# Power.net
KiCad netlist of a schematic drawn in Altium Designer
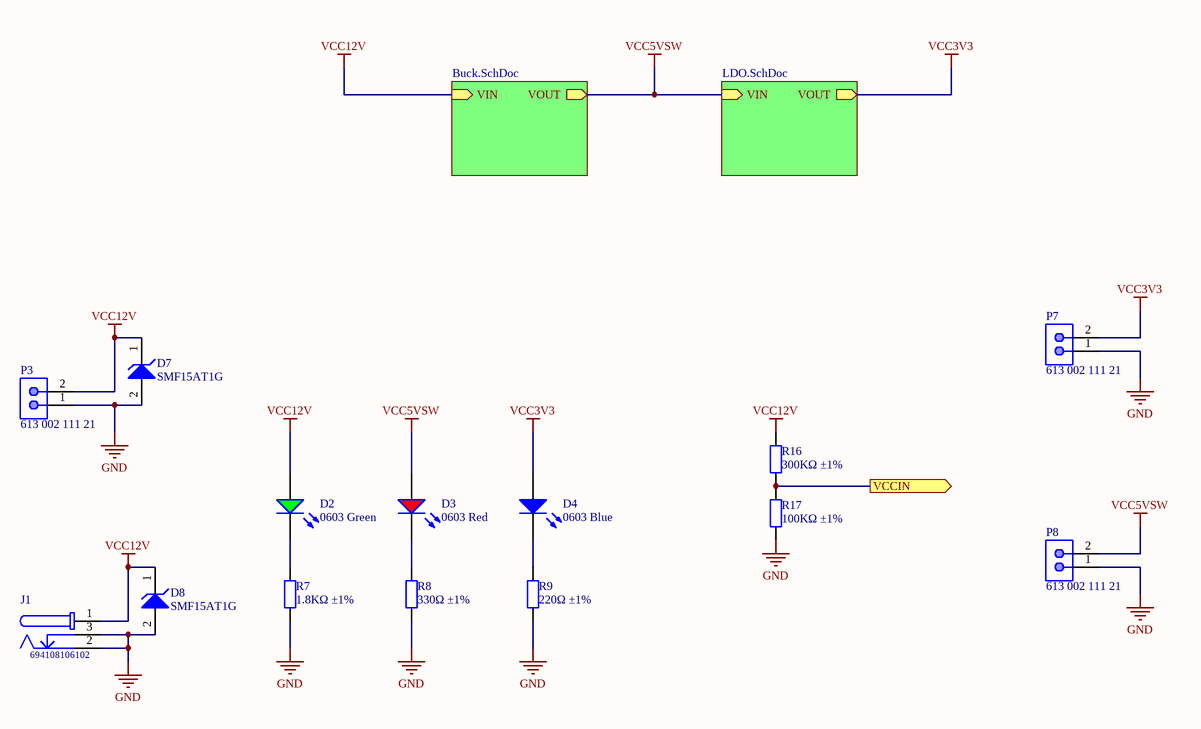
[diagram p0: Power.SchDoc]

(export (version "E")
  (design (tool "Eeschema 10.0.6"))
  (components
    (comp (ref "D2")
      (value "0603 Green")
      (footprint "0603_LED_S1")
      (description "LED")
      (libsource (lib "Miscellaneous Devices LC") (part "0603 LED Green"))
    )
    (comp (ref "D3")
      (value "0603 Red")
      (footprint "0603_LED_S1")
      (description "LED")
      (libsource (lib "Miscellaneous Devices LC") (part "0603 LED Red"))
    )
    (comp (ref "D4")
      (value "0603 Blue")
      (footprint "0603_LED_S1")
      (description "LED")
      (libsource (lib "Miscellaneous Devices LC") (part "0603 LED Blue"))
    )
    (comp (ref "D7")
      (value "SMF15AT1G")
      (footprint "ONSC-SOD-123FL-2-498_V")
      (description "200 W Transient Voltage Suppressor, 2-Pin SOD-123FL, Pb-Free, Tape and Reel")
      (fields (field (name "MANUFACTURER") "On Semiconductor"))
      (libsource (lib "Altium Content Vault") (part "ONSC-K1A2-2"))
    )
    (comp (ref "D8")
      (value "SMF15AT1G")
      (footprint "ONSC-SOD-123FL-2-498_V")
      (description "200 W Transient Voltage Suppressor, 2-Pin SOD-123FL, Pb-Free, Tape and Reel")
      (fields (field (name "MANUFACTURER") "On Semiconductor"))
      (libsource (lib "Altium Content Vault") (part "ONSC-K1A2-2"))
    )
    (comp (ref "J1")
      (value "694108106102")
      (footprint "694108106102")
      (description "DC Power Jack Connector with 4 soldering pads & Pegs WR-DC, Male, Right Angled, SMT, 5 A, 24 V")
      (fields (field (name "MANUFACTURER") "Wurth Elektronik") (field (name "PUBLISHER") "WurthElektronik"))
      (libsource (lib "Altium Content Vault") (part "WE-JACK-2CD3-RN"))
    )
    (comp (ref "P3")
      (value "613 002 111 21")
      (footprint "WE-61300211121_V")
      (libsource (lib "Altium Content Vault") (part "CN-1P-M-R2"))
    )
    (comp (ref "P7")
      (value "613 002 111 21")
      (footprint "WE-61300211121_V")
      (libsource (lib "Altium Content Vault") (part "CN-1P-M-R2"))
    )
    (comp (ref "P8")
      (value "613 002 111 21")
      (footprint "WE-61300211121_V")
      (libsource (lib "Altium Content Vault") (part "CN-1P-M-R2"))
    )
    (comp (ref "R7")
      (value "1.8KΩ ±1%")
      (footprint "0603_R")
      (description "Chip resistor")
      (fields (field (name "MANUFACTURER") "Uniroyal Elec") (field (name "PARTNUMBER") "0603WAF1801T5E"))
      (libsource (lib "Miscellaneous Devices LC") (part "0603 1.8K (1801) 1%"))
    )
    (comp (ref "R8")
      (value "330Ω ±1%")
      (footprint "0603_R")
      (description "Chip resistor")
      (fields (field (name "MANUFACTURER") "Uniroyal Elec") (field (name "PARTNUMBER") "0603WAF3300T5E"))
      (libsource (lib "Miscellaneous Devices LC") (part "0603 330R (3300) 1%"))
    )
    (comp (ref "R9")
      (value "220Ω ±1%")
      (footprint "0603_R")
      (description "Chip resistor")
      (fields (field (name "MANUFACTURER") "Uniroyal Elec") (field (name "PARTNUMBER") "0603WAF2200T5E"))
      (libsource (lib "Miscellaneous Devices LC") (part "0603 220R (2200) 1%"))
    )
    (comp (ref "R16")
      (value "300KΩ ±1%")
      (footprint "0402_R")
      (description "Chip resistor")
      (fields (field (name "MANUFACTURER") "Uniroyal Elec") (field (name "PARTNUMBER") "0402WGF3003TCE"))
      (libsource (lib "Miscellaneous Devices LC") (part "0402 300K (3003) 1%"))
    )
    (comp (ref "R17")
      (value "100KΩ ±1%")
      (footprint "0402_R")
      (description "Chip resistor")
      (fields (field (name "MANUFACTURER") "Uniroyal Elec") (field (name "PARTNUMBER") "0402WGF1003TCE"))
      (libsource (lib "Miscellaneous Devices LC") (part "0402 100K (1003) 1%"))
    )
  )
  (nets
    (net (code "1") (name "/VCCIN") (class "Default")
      (node (ref "R16") (pin "1") (pinfunction "1_1") (pintype "passive"))
      (node (ref "R17") (pin "2") (pinfunction "2_2") (pintype "passive"))
    )
    (net (code "2") (name "GND") (class "Default")
      (node (ref "D7") (pin "2") (pinfunction "A_2") (pintype "passive"))
      (node (ref "D8") (pin "2") (pinfunction "A_2") (pintype "passive"))
      (node (ref "J1") (pin "2") (pinfunction "2_2") (pintype "passive"))
      (node (ref "J1") (pin "3") (pinfunction "3_3") (pintype "passive"))
      (node (ref "P3") (pin "1") (pinfunction "1_1") (pintype "passive"))
      (node (ref "P7") (pin "1") (pinfunction "1_1") (pintype "passive"))
      (node (ref "P8") (pin "1") (pinfunction "1_1") (pintype "passive"))
      (node (ref "R17") (pin "1") (pinfunction "1_1") (pintype "passive"))
      (node (ref "R7") (pin "1") (pinfunction "1_1") (pintype "passive"))
      (node (ref "R8") (pin "1") (pinfunction "1_1") (pintype "passive"))
      (node (ref "R9") (pin "1") (pinfunction "1_1") (pintype "passive"))
    )
    (net (code "3") (name "Net-(D2-PadK)") (class "Default")
      (node (ref "D2") (pin "K") (pinfunction "K_K") (pintype "passive"))
      (node (ref "R7") (pin "2") (pinfunction "2_2") (pintype "passive"))
    )
    (net (code "4") (name "Net-(D3-PadK)") (class "Default")
      (node (ref "D3") (pin "K") (pinfunction "K_K") (pintype "passive"))
      (node (ref "R8") (pin "2") (pinfunction "2_2") (pintype "passive"))
    )
    (net (code "5") (name "Net-(D4-PadK)") (class "Default")
      (node (ref "D4") (pin "K") (pinfunction "K_K") (pintype "passive"))
      (node (ref "R9") (pin "2") (pinfunction "2_2") (pintype "passive"))
    )
    (net (code "6") (name "VCC3V3") (class "Default")
      (node (ref "D4") (pin "A") (pinfunction "A_A") (pintype "passive"))
      (node (ref "P7") (pin "2") (pinfunction "2_2") (pintype "passive"))
    )
    (net (code "7") (name "VCC5VSW") (class "Default")
      (node (ref "D3") (pin "A") (pinfunction "A_A") (pintype "passive"))
      (node (ref "P8") (pin "2") (pinfunction "2_2") (pintype "passive"))
    )
    (net (code "8") (name "VCC12V") (class "Default")
      (node (ref "D2") (pin "A") (pinfunction "A_A") (pintype "passive"))
      (node (ref "D7") (pin "1") (pinfunction "K_1") (pintype "passive"))
      (node (ref "D8") (pin "1") (pinfunction "K_1") (pintype "passive"))
      (node (ref "J1") (pin "1") (pinfunction "1_1") (pintype "passive"))
      (node (ref "P3") (pin "2") (pinfunction "2_2") (pintype "passive"))
      (node (ref "R16") (pin "2") (pinfunction "2_2") (pintype "passive"))
    )
  )
)
